# BaseBoard.net
KiCad netlist of a schematic drawn in EAGLE
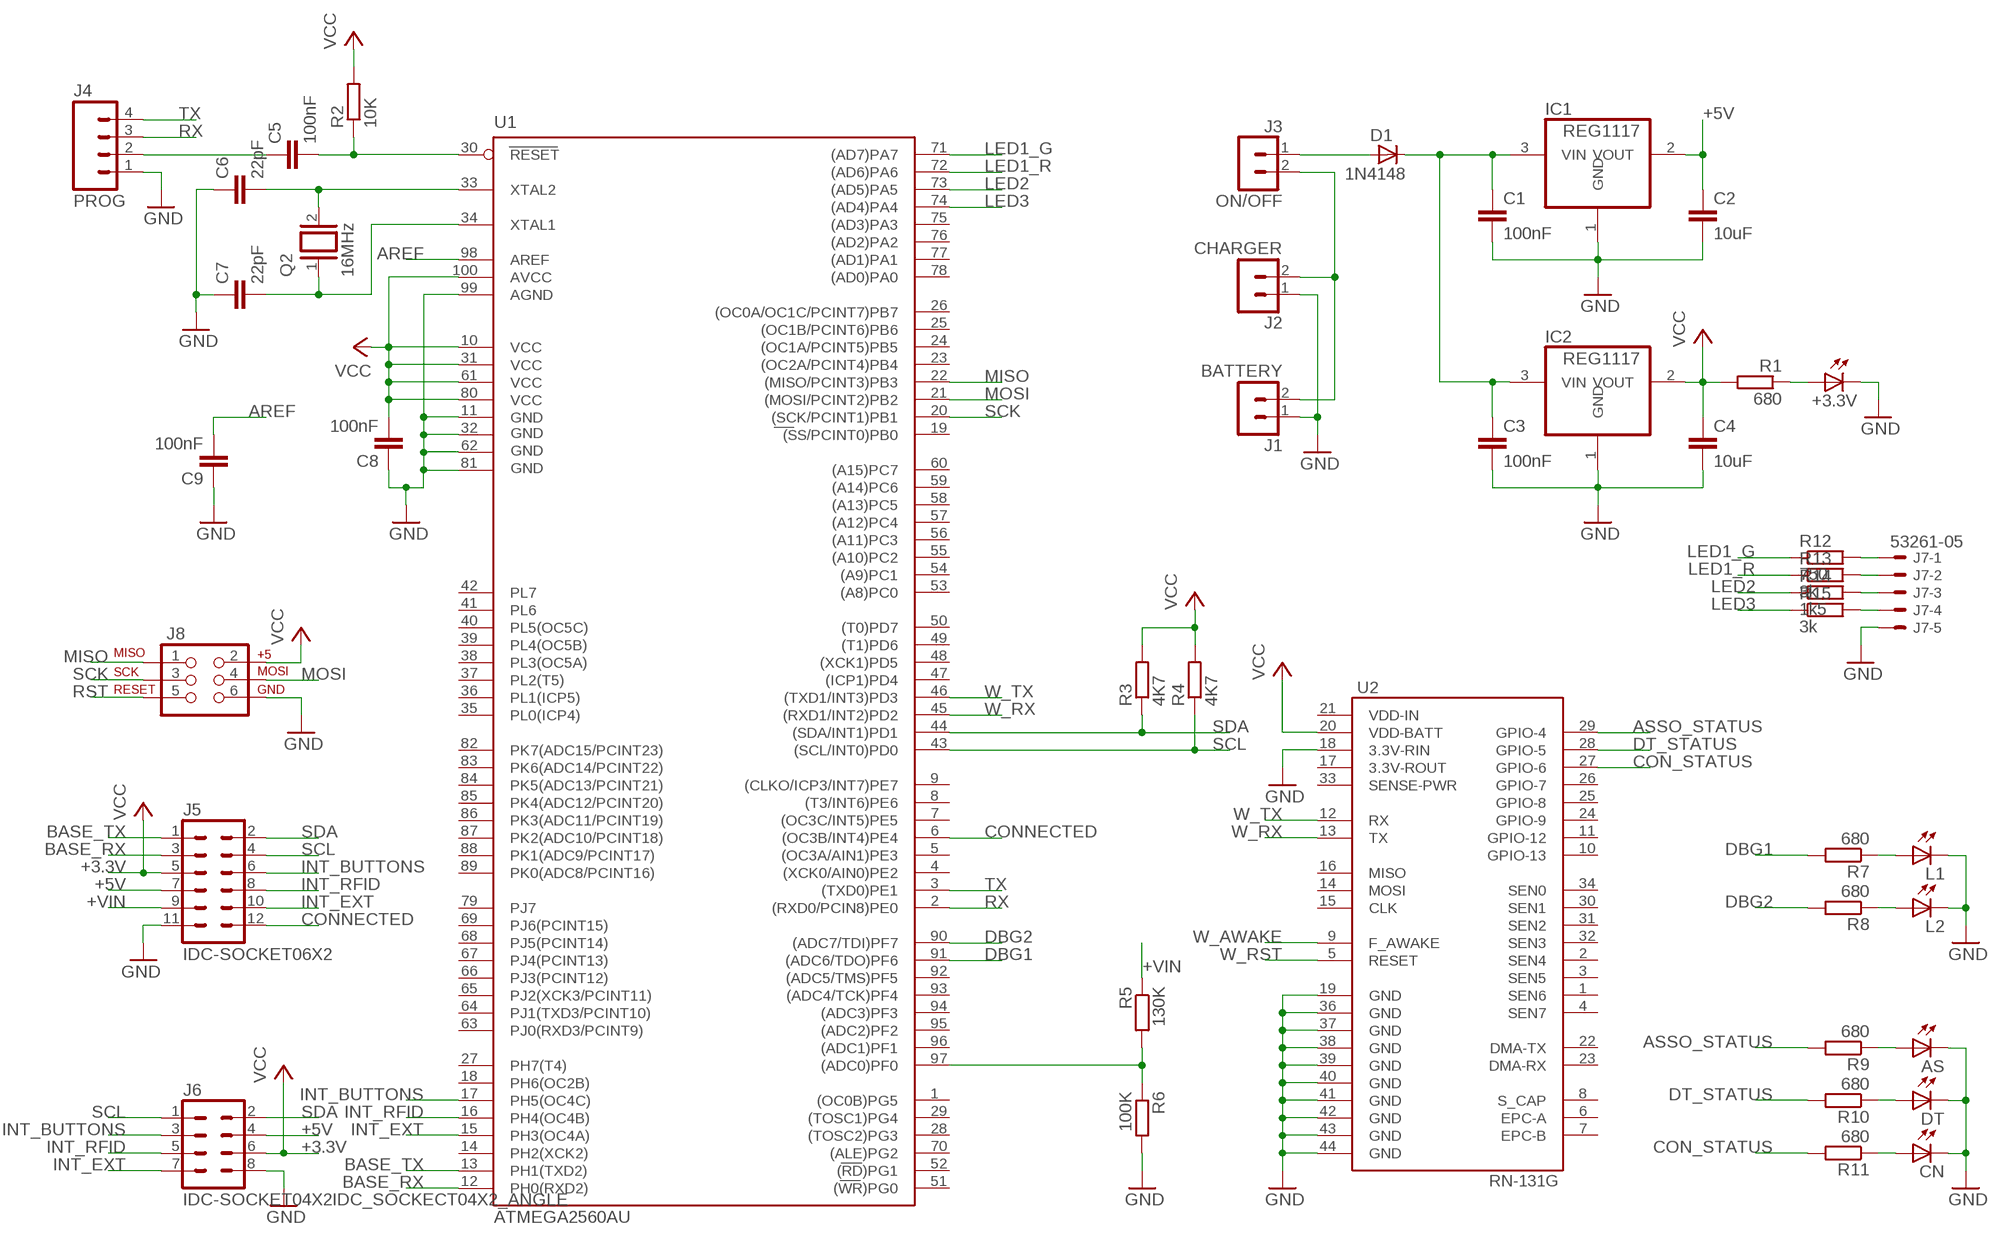
[diagram p0: schematic, sheet 1]

(export (version "E")
  (design (tool "Eeschema 10.0.6"))
  (components
    (comp (ref "+3.3V")
      (value "LEDSML0805")
      (footprint "eagle-import:SML0805")
      (libsource (lib "eagle-import") (part "LEDSML0805"))
    )
    (comp (ref "AS")
      (value "LEDSML0805")
      (footprint "eagle-import:SML0805")
      (libsource (lib "eagle-import") (part "LEDSML0805"))
    )
    (comp (ref "C1")
      (value "100nF")
      (footprint "eagle-import:C0805")
      (libsource (lib "eagle-import") (part "C-EUC0805"))
    )
    (comp (ref "C2")
      (value "10uF")
      (footprint "eagle-import:C0805")
      (libsource (lib "eagle-import") (part "C-EUC0805"))
    )
    (comp (ref "C3")
      (value "100nF")
      (footprint "eagle-import:C0805")
      (libsource (lib "eagle-import") (part "C-EUC0805"))
    )
    (comp (ref "C4")
      (value "10uF")
      (footprint "eagle-import:C0805")
      (libsource (lib "eagle-import") (part "C-EUC0805"))
    )
    (comp (ref "C5")
      (value "100nF")
      (footprint "eagle-import:C0805")
      (libsource (lib "eagle-import") (part "C-EUC0805"))
    )
    (comp (ref "C6")
      (value "22pF")
      (footprint "eagle-import:C0805")
      (libsource (lib "eagle-import") (part "C-EUC0805"))
    )
    (comp (ref "C7")
      (value "22pF")
      (footprint "eagle-import:C0805")
      (libsource (lib "eagle-import") (part "C-EUC0805"))
    )
    (comp (ref "C8")
      (value "100nF")
      (footprint "eagle-import:C0805")
      (libsource (lib "eagle-import") (part "C-EUC0805"))
    )
    (comp (ref "C9")
      (value "100nF")
      (footprint "eagle-import:C0805")
      (libsource (lib "eagle-import") (part "C-EUC0805"))
    )
    (comp (ref "CN")
      (value "LEDSML0805")
      (footprint "eagle-import:SML0805")
      (libsource (lib "eagle-import") (part "LEDSML0805"))
    )
    (comp (ref "D1")
      (value "1N4148")
      (footprint "eagle-import:D0805")
      (libsource (lib "eagle-import") (part "1N4148"))
    )
    (comp (ref "DT")
      (value "LEDSML0805")
      (footprint "eagle-import:SML0805")
      (libsource (lib "eagle-import") (part "LEDSML0805"))
    )
    (comp (ref "IC1")
      (value "REG1117")
      (footprint "eagle-import:SOT223")
      (libsource (lib "eagle-import") (part "REG1117"))
    )
    (comp (ref "IC2")
      (value "REG1117")
      (footprint "eagle-import:SOT223")
      (libsource (lib "eagle-import") (part "REG1117"))
    )
    (comp (ref "J1")
      (value "BATTERY")
      (footprint "eagle-import:CON_2P_SMD")
      (libsource (lib "eagle-import") (part "CON02"))
    )
    (comp (ref "J2")
      (value "CHARGER")
      (footprint "eagle-import:CON_2P_SMD")
      (libsource (lib "eagle-import") (part "CON02"))
    )
    (comp (ref "J3")
      (value "ON/OFF")
      (footprint "eagle-import:CON_2P_SMD")
      (libsource (lib "eagle-import") (part "CON02"))
    )
    (comp (ref "J4")
      (value "PROG")
      (footprint "eagle-import:1X04")
      (libsource (lib "eagle-import") (part "M04PTH"))
    )
    (comp (ref "J5")
      (value "IDC-SOCKET06X2")
      (footprint "eagle-import:SOCKET06X2")
      (libsource (lib "eagle-import") (part "IDC-SOCKET06X2"))
    )
    (comp (ref "J6")
      (value "IDC-SOCKET04X2IDC_SOCKECT04X2_ANGLE")
      (footprint "eagle-import:SOCKET04X2_ANGLE")
      (libsource (lib "eagle-import") (part "IDC-SOCKET04X2IDC_SOCKECT04X2_ANGLE"))
    )
    (comp (ref "J7")
      (value "53261-05")
      (footprint "eagle-import:53261-05")
      (libsource (lib "eagle-import") (part "53?-05261"))
    )
    (comp (ref "J8")
      (value "AVR_SPI_PRG_6NS")
      (footprint "eagle-import:2X3-NS")
      (libsource (lib "eagle-import") (part "AVR_SPI_PRG_6NS"))
    )
    (comp (ref "L1")
      (value "LEDSML0805")
      (footprint "eagle-import:SML0805")
      (libsource (lib "eagle-import") (part "LEDSML0805"))
    )
    (comp (ref "L2")
      (value "LEDSML0805")
      (footprint "eagle-import:SML0805")
      (libsource (lib "eagle-import") (part "LEDSML0805"))
    )
    (comp (ref "Q2")
      (value "16MHz")
      (footprint "eagle-import:QS")
      (libsource (lib "eagle-import") (part "XTAL/S"))
    )
    (comp (ref "R1")
      (value "680")
      (footprint "eagle-import:R0805")
      (libsource (lib "eagle-import") (part "R-EU_R0805"))
    )
    (comp (ref "R2")
      (value "10K")
      (footprint "eagle-import:R0805")
      (libsource (lib "eagle-import") (part "R-EU_R0805"))
    )
    (comp (ref "R3")
      (value "4K7")
      (footprint "eagle-import:R0805")
      (libsource (lib "eagle-import") (part "R-EU_R0805"))
    )
    (comp (ref "R4")
      (value "4K7")
      (footprint "eagle-import:R0805")
      (libsource (lib "eagle-import") (part "R-EU_R0805"))
    )
    (comp (ref "R5")
      (value "130K")
      (footprint "eagle-import:R0805")
      (libsource (lib "eagle-import") (part "R-EU_R0805"))
    )
    (comp (ref "R6")
      (value "100K")
      (footprint "eagle-import:R0805")
      (libsource (lib "eagle-import") (part "R-EU_R0805"))
    )
    (comp (ref "R7")
      (value "680")
      (footprint "eagle-import:R0805")
      (libsource (lib "eagle-import") (part "R-EU_R0805"))
    )
    (comp (ref "R8")
      (value "680")
      (footprint "eagle-import:R0805")
      (libsource (lib "eagle-import") (part "R-EU_R0805"))
    )
    (comp (ref "R9")
      (value "680")
      (footprint "eagle-import:R0805")
      (libsource (lib "eagle-import") (part "R-EU_R0805"))
    )
    (comp (ref "R10")
      (value "680")
      (footprint "eagle-import:R0805")
      (libsource (lib "eagle-import") (part "R-EU_R0805"))
    )
    (comp (ref "R11")
      (value "680")
      (footprint "eagle-import:R0805")
      (libsource (lib "eagle-import") (part "R-EU_R0805"))
    )
    (comp (ref "R12")
      (value "750")
      (footprint "eagle-import:R0805")
      (libsource (lib "eagle-import") (part "R-EU_R0805"))
    )
    (comp (ref "R13")
      (value "3k")
      (footprint "eagle-import:R0805")
      (libsource (lib "eagle-import") (part "R-EU_R0805"))
    )
    (comp (ref "R14")
      (value "1k5")
      (footprint "eagle-import:R0805")
      (libsource (lib "eagle-import") (part "R-EU_R0805"))
    )
    (comp (ref "R15")
      (value "3k")
      (footprint "eagle-import:R0805")
      (libsource (lib "eagle-import") (part "R-EU_R0805"))
    )
    (comp (ref "U1")
      (value "ATMEGA2560AU")
      (footprint "eagle-import:TQFP100")
      (libsource (lib "eagle-import") (part "ATMEGA2560AU"))
    )
    (comp (ref "U2")
      (value "RN-131G")
      (footprint "eagle-import:RN-131G")
      (libsource (lib "eagle-import") (part "RN-131G"))
    )
  )
  (nets
    (net (code "1") (name "/+5V") (class "Default")
      (node (ref "C2") (pin "1") (pinfunction "1_1") (pintype "passive"))
      (node (ref "IC1") (pin "2") (pinfunction "VOUT_2") (pintype "output"))
      (node (ref "J5") (pin "7") (pinfunction "7_7") (pintype "passive"))
      (node (ref "J6") (pin "4") (pinfunction "4_4") (pintype "passive"))
    )
    (net (code "2") (name "/+VIN") (class "Default")
      (node (ref "C1") (pin "1") (pinfunction "1_1") (pintype "passive"))
      (node (ref "C3") (pin "1") (pinfunction "1_1") (pintype "passive"))
      (node (ref "D1") (pin "C") (pinfunction "C_C") (pintype "passive"))
      (node (ref "IC1") (pin "3") (pinfunction "VIN_3") (pintype "input"))
      (node (ref "IC2") (pin "3") (pinfunction "VIN_3") (pintype "input"))
      (node (ref "J5") (pin "9") (pinfunction "9_9") (pintype "passive"))
      (node (ref "R5") (pin "1") (pinfunction "1_1") (pintype "passive"))
    )
    (net (code "3") (name "/AREF") (class "Default")
      (node (ref "C9") (pin "2") (pinfunction "2_2") (pintype "passive"))
      (node (ref "U1") (pin "98") (pinfunction "AREF_98") (pintype "bidirectional"))
    )
    (net (code "4") (name "/ASSO_STATUS") (class "Default")
      (node (ref "R9") (pin "2") (pinfunction "2_2") (pintype "passive"))
      (node (ref "U2") (pin "29") (pinfunction "GPIO-4_29") (pintype "bidirectional"))
    )
    (net (code "5") (name "/BASE_RX") (class "Default")
      (node (ref "J5") (pin "3") (pinfunction "3_3") (pintype "passive"))
      (node (ref "U1") (pin "12") (pinfunction "PH0(RXD2)_12") (pintype "bidirectional"))
    )
    (net (code "6") (name "/BASE_TX") (class "Default")
      (node (ref "J5") (pin "1") (pinfunction "1_1") (pintype "passive"))
      (node (ref "U1") (pin "13") (pinfunction "PH1(TXD2)_13") (pintype "bidirectional"))
    )
    (net (code "7") (name "/CONNECTED") (class "Default")
      (node (ref "J5") (pin "12") (pinfunction "12_12") (pintype "passive"))
      (node (ref "U1") (pin "6") (pinfunction "(OC3B/INT4)PE4_6") (pintype "bidirectional"))
    )
    (net (code "8") (name "/CON_STATUS") (class "Default")
      (node (ref "R11") (pin "2") (pinfunction "2_2") (pintype "passive"))
      (node (ref "U2") (pin "27") (pinfunction "GPIO-6_27") (pintype "bidirectional"))
    )
    (net (code "9") (name "/DBG1") (class "Default")
      (node (ref "R7") (pin "2") (pinfunction "2_2") (pintype "passive"))
      (node (ref "U1") (pin "91") (pinfunction "(ADC6/TDO)PF6_91") (pintype "bidirectional"))
    )
    (net (code "10") (name "/DBG2") (class "Default")
      (node (ref "R8") (pin "2") (pinfunction "2_2") (pintype "passive"))
      (node (ref "U1") (pin "90") (pinfunction "(ADC7/TDI)PF7_90") (pintype "bidirectional"))
    )
    (net (code "11") (name "/DT_STATUS") (class "Default")
      (node (ref "R10") (pin "2") (pinfunction "2_2") (pintype "passive"))
      (node (ref "U2") (pin "28") (pinfunction "GPIO-5_28") (pintype "bidirectional"))
    )
    (net (code "12") (name "/INT_BUTTONS") (class "Default")
      (node (ref "J5") (pin "6") (pinfunction "6_6") (pintype "passive"))
      (node (ref "J6") (pin "3") (pinfunction "3_3") (pintype "passive"))
      (node (ref "U1") (pin "17") (pinfunction "PH5(OC4C)_17") (pintype "bidirectional"))
    )
    (net (code "13") (name "/INT_EXT") (class "Default")
      (node (ref "J5") (pin "10") (pinfunction "10_10") (pintype "passive"))
      (node (ref "J6") (pin "7") (pinfunction "7_7") (pintype "passive"))
      (node (ref "U1") (pin "15") (pinfunction "PH3(OC4A)_15") (pintype "bidirectional"))
    )
    (net (code "14") (name "/INT_RFID") (class "Default")
      (node (ref "J5") (pin "8") (pinfunction "8_8") (pintype "passive"))
      (node (ref "J6") (pin "5") (pinfunction "5_5") (pintype "passive"))
      (node (ref "U1") (pin "16") (pinfunction "PH4(OC4B)_16") (pintype "bidirectional"))
    )
    (net (code "15") (name "/LED1_G") (class "Default")
      (node (ref "R12") (pin "1") (pinfunction "1_1") (pintype "passive"))
      (node (ref "U1") (pin "71") (pinfunction "(AD7)PA7_71") (pintype "bidirectional"))
    )
    (net (code "16") (name "/LED1_R") (class "Default")
      (node (ref "R13") (pin "1") (pinfunction "1_1") (pintype "passive"))
      (node (ref "U1") (pin "72") (pinfunction "(AD6)PA6_72") (pintype "bidirectional"))
    )
    (net (code "17") (name "/LED2") (class "Default")
      (node (ref "R14") (pin "1") (pinfunction "1_1") (pintype "passive"))
      (node (ref "U1") (pin "73") (pinfunction "(AD5)PA5_73") (pintype "bidirectional"))
    )
    (net (code "18") (name "/LED3") (class "Default")
      (node (ref "R15") (pin "1") (pinfunction "1_1") (pintype "passive"))
      (node (ref "U1") (pin "74") (pinfunction "(AD4)PA4_74") (pintype "bidirectional"))
    )
    (net (code "19") (name "/MISO") (class "Default")
      (node (ref "J8") (pin "1") (pinfunction "1_1") (pintype "passive"))
      (node (ref "U1") (pin "22") (pinfunction "(MISO/PCINT3)PB3_22") (pintype "bidirectional"))
    )
    (net (code "20") (name "/MOSI") (class "Default")
      (node (ref "J8") (pin "4") (pinfunction "4_4") (pintype "passive"))
      (node (ref "U1") (pin "21") (pinfunction "(MOSI/PCINT2)PB2_21") (pintype "bidirectional"))
    )
    (net (code "21") (name "/RST") (class "Default")
      (node (ref "C5") (pin "2") (pinfunction "2_2") (pintype "passive"))
      (node (ref "J8") (pin "5") (pinfunction "5_5") (pintype "passive"))
      (node (ref "R2") (pin "1") (pinfunction "1_1") (pintype "passive"))
      (node (ref "U1") (pin "30") (pinfunction "RESET_30") (pintype "input"))
    )
    (net (code "22") (name "/RX") (class "Default")
      (node (ref "J4") (pin "3") (pinfunction "3_3") (pintype "passive"))
      (node (ref "U1") (pin "2") (pinfunction "(RXD0/PCIN8)PE0_2") (pintype "bidirectional"))
    )
    (net (code "23") (name "/SCK") (class "Default")
      (node (ref "J8") (pin "3") (pinfunction "3_3") (pintype "passive"))
      (node (ref "U1") (pin "20") (pinfunction "(SCK/PCINT1)PB1_20") (pintype "bidirectional"))
    )
    (net (code "24") (name "/SCL") (class "Default")
      (node (ref "J5") (pin "4") (pinfunction "4_4") (pintype "passive"))
      (node (ref "J6") (pin "1") (pinfunction "1_1") (pintype "passive"))
      (node (ref "R4") (pin "1") (pinfunction "1_1") (pintype "passive"))
      (node (ref "U1") (pin "43") (pinfunction "(SCL/INT0)PD0_43") (pintype "bidirectional"))
    )
    (net (code "25") (name "/SDA") (class "Default")
      (node (ref "J5") (pin "2") (pinfunction "2_2") (pintype "passive"))
      (node (ref "J6") (pin "2") (pinfunction "2_2") (pintype "passive"))
      (node (ref "R3") (pin "1") (pinfunction "1_1") (pintype "passive"))
      (node (ref "U1") (pin "44") (pinfunction "(SDA/INT1)PD1_44") (pintype "bidirectional"))
    )
    (net (code "26") (name "/TX") (class "Default")
      (node (ref "J4") (pin "4") (pinfunction "4_4") (pintype "passive"))
      (node (ref "U1") (pin "3") (pinfunction "(TXD0)PE1_3") (pintype "bidirectional"))
    )
    (net (code "27") (name "/W_AWAKE") (class "Default")
      (node (ref "U2") (pin "9") (pinfunction "F_AWAKE_9") (pintype "bidirectional"))
    )
    (net (code "28") (name "/W_RST") (class "Default")
      (node (ref "U2") (pin "5") (pinfunction "RESET_5") (pintype "bidirectional"))
    )
    (net (code "29") (name "/W_RX") (class "Default")
      (node (ref "U1") (pin "45") (pinfunction "(RXD1/INT2)PD2_45") (pintype "bidirectional"))
      (node (ref "U2") (pin "13") (pinfunction "TX_13") (pintype "bidirectional"))
    )
    (net (code "30") (name "/W_TX") (class "Default")
      (node (ref "U1") (pin "46") (pinfunction "(TXD1/INT3)PD3_46") (pintype "bidirectional"))
      (node (ref "U2") (pin "12") (pinfunction "RX_12") (pintype "bidirectional"))
    )
    (net (code "31") (name "GND") (class "Default")
      (node (ref "+3.3V") (pin "C") (pinfunction "C_C") (pintype "passive"))
      (node (ref "AS") (pin "C") (pinfunction "C_C") (pintype "passive"))
      (node (ref "C1") (pin "2") (pinfunction "2_2") (pintype "passive"))
      (node (ref "C2") (pin "2") (pinfunction "2_2") (pintype "passive"))
      (node (ref "C3") (pin "2") (pinfunction "2_2") (pintype "passive"))
      (node (ref "C4") (pin "2") (pinfunction "2_2") (pintype "passive"))
      (node (ref "C6") (pin "1") (pinfunction "1_1") (pintype "passive"))
      (node (ref "C7") (pin "1") (pinfunction "1_1") (pintype "passive"))
      (node (ref "C8") (pin "1") (pinfunction "1_1") (pintype "passive"))
      (node (ref "C9") (pin "1") (pinfunction "1_1") (pintype "passive"))
      (node (ref "CN") (pin "C") (pinfunction "C_C") (pintype "passive"))
      (node (ref "DT") (pin "C") (pinfunction "C_C") (pintype "passive"))
      (node (ref "IC1") (pin "1") (pinfunction "GND_1") (pintype "power_in"))
      (node (ref "IC2") (pin "1") (pinfunction "GND_1") (pintype "power_in"))
      (node (ref "J1") (pin "1") (pinfunction "1_1") (pintype "passive"))
      (node (ref "J2") (pin "1") (pinfunction "1_1") (pintype "passive"))
      (node (ref "J4") (pin "1") (pinfunction "1_1") (pintype "passive"))
      (node (ref "J5") (pin "11") (pinfunction "11_11") (pintype "passive"))
      (node (ref "J6") (pin "8") (pinfunction "8_8") (pintype "passive"))
      (node (ref "J7") (pin "5") (pinfunction "S_5") (pintype "passive"))
      (node (ref "J8") (pin "6") (pinfunction "6_6") (pintype "passive"))
      (node (ref "L1") (pin "C") (pinfunction "C_C") (pintype "passive"))
      (node (ref "L2") (pin "C") (pinfunction "C_C") (pintype "passive"))
      (node (ref "R6") (pin "2") (pinfunction "2_2") (pintype "passive"))
      (node (ref "U1") (pin "11") (pinfunction "GND_11") (pintype "power_in"))
      (node (ref "U1") (pin "32") (pinfunction "GND1_32") (pintype "power_in"))
      (node (ref "U1") (pin "62") (pinfunction "GND2_62") (pintype "power_in"))
      (node (ref "U1") (pin "81") (pinfunction "GND3_81") (pintype "power_in"))
      (node (ref "U1") (pin "99") (pinfunction "AGND_99") (pintype "power_in"))
      (node (ref "U2") (pin "18") (pinfunction "3.3V-RIN_18") (pintype "bidirectional"))
      (node (ref "U2") (pin "19") (pinfunction "GND_19") (pintype "bidirectional"))
      (node (ref "U2") (pin "36") (pinfunction "GND_36") (pintype "bidirectional"))
      (node (ref "U2") (pin "37") (pinfunction "GND_37") (pintype "bidirectional"))
      (node (ref "U2") (pin "38") (pinfunction "GND_38") (pintype "bidirectional"))
      (node (ref "U2") (pin "39") (pinfunction "GND_39") (pintype "bidirectional"))
      (node (ref "U2") (pin "40") (pinfunction "GND_40") (pintype "bidirectional"))
      (node (ref "U2") (pin "41") (pinfunction "GND_41") (pintype "bidirectional"))
      (node (ref "U2") (pin "42") (pinfunction "GND_42") (pintype "bidirectional"))
      (node (ref "U2") (pin "43") (pinfunction "GND_43") (pintype "bidirectional"))
      (node (ref "U2") (pin "44") (pinfunction "GND_44") (pintype "bidirectional"))
    )
    (net (code "32") (name "Net-(+3.3V-PadA)") (class "Default")
      (node (ref "+3.3V") (pin "A") (pinfunction "A_A") (pintype "passive"))
      (node (ref "R1") (pin "1") (pinfunction "1_1") (pintype "passive"))
    )
    (net (code "33") (name "Net-(AS-PadA)") (class "Default")
      (node (ref "AS") (pin "A") (pinfunction "A_A") (pintype "passive"))
      (node (ref "R9") (pin "1") (pinfunction "1_1") (pintype "passive"))
    )
    (net (code "34") (name "Net-(C5-Pad1)") (class "Default")
      (node (ref "C5") (pin "1") (pinfunction "1_1") (pintype "passive"))
      (node (ref "J4") (pin "2") (pinfunction "2_2") (pintype "passive"))
    )
    (net (code "35") (name "Net-(CN-PadA)") (class "Default")
      (node (ref "CN") (pin "A") (pinfunction "A_A") (pintype "passive"))
      (node (ref "R11") (pin "1") (pinfunction "1_1") (pintype "passive"))
    )
    (net (code "36") (name "Net-(D1-PadA)") (class "Default")
      (node (ref "D1") (pin "A") (pinfunction "A_A") (pintype "passive"))
      (node (ref "J3") (pin "1") (pinfunction "1_1") (pintype "passive"))
    )
    (net (code "37") (name "Net-(DT-PadA)") (class "Default")
      (node (ref "DT") (pin "A") (pinfunction "A_A") (pintype "passive"))
      (node (ref "R10") (pin "1") (pinfunction "1_1") (pintype "passive"))
    )
    (net (code "38") (name "Net-(J1-Pad2)") (class "Default")
      (node (ref "J1") (pin "2") (pinfunction "2_2") (pintype "passive"))
      (node (ref "J2") (pin "2") (pinfunction "2_2") (pintype "passive"))
      (node (ref "J3") (pin "2") (pinfunction "2_2") (pintype "passive"))
    )
    (net (code "39") (name "Net-(J7A-S)") (class "Default")
      (node (ref "J7") (pin "1") (pinfunction "S_1") (pintype "passive"))
      (node (ref "R12") (pin "2") (pinfunction "2_2") (pintype "passive"))
    )
    (net (code "40") (name "Net-(J7B-S)") (class "Default")
      (node (ref "J7") (pin "2") (pinfunction "S_2") (pintype "passive"))
      (node (ref "R13") (pin "2") (pinfunction "2_2") (pintype "passive"))
    )
    (net (code "41") (name "Net-(J7C-S)") (class "Default")
      (node (ref "J7") (pin "3") (pinfunction "S_3") (pintype "passive"))
      (node (ref "R14") (pin "2") (pinfunction "2_2") (pintype "passive"))
    )
    (net (code "42") (name "Net-(J7D-S)") (class "Default")
      (node (ref "J7") (pin "4") (pinfunction "S_4") (pintype "passive"))
      (node (ref "R15") (pin "2") (pinfunction "2_2") (pintype "passive"))
    )
    (net (code "43") (name "Net-(L1-PadA)") (class "Default")
      (node (ref "L1") (pin "A") (pinfunction "A_A") (pintype "passive"))
      (node (ref "R7") (pin "1") (pinfunction "1_1") (pintype "passive"))
    )
    (net (code "44") (name "Net-(L2-PadA)") (class "Default")
      (node (ref "L2") (pin "A") (pinfunction "A_A") (pintype "passive"))
      (node (ref "R8") (pin "1") (pinfunction "1_1") (pintype "passive"))
    )
    (net (code "45") (name "Net-(U1-(ADC0)PF0)") (class "Default")
      (node (ref "R5") (pin "2") (pinfunction "2_2") (pintype "passive"))
      (node (ref "R6") (pin "1") (pinfunction "1_1") (pintype "passive"))
      (node (ref "U1") (pin "97") (pinfunction "(ADC0)PF0_97") (pintype "bidirectional"))
    )
    (net (code "46") (name "Net-(U1-XTAL1)") (class "Default")
      (node (ref "C7") (pin "2") (pinfunction "2_2") (pintype "passive"))
      (node (ref "Q2") (pin "1") (pinfunction "1_1") (pintype "passive"))
      (node (ref "U1") (pin "34") (pinfunction "XTAL1_34") (pintype "input"))
    )
    (net (code "47") (name "Net-(U1-XTAL2)") (class "Default")
      (node (ref "C6") (pin "2") (pinfunction "2_2") (pintype "passive"))
      (node (ref "Q2") (pin "2") (pinfunction "2_2") (pintype "passive"))
      (node (ref "U1") (pin "33") (pinfunction "XTAL2_33") (pintype "output"))
    )
    (net (code "48") (name "VCC") (class "Default")
      (node (ref "C4") (pin "1") (pinfunction "1_1") (pintype "passive"))
      (node (ref "C8") (pin "2") (pinfunction "2_2") (pintype "passive"))
      (node (ref "IC2") (pin "2") (pinfunction "VOUT_2") (pintype "output"))
      (node (ref "J5") (pin "5") (pinfunction "5_5") (pintype "passive"))
      (node (ref "J6") (pin "6") (pinfunction "6_6") (pintype "passive"))
      (node (ref "J8") (pin "2") (pinfunction "2_2") (pintype "passive"))
      (node (ref "R1") (pin "2") (pinfunction "2_2") (pintype "passive"))
      (node (ref "R2") (pin "2") (pinfunction "2_2") (pintype "passive"))
      (node (ref "R3") (pin "2") (pinfunction "2_2") (pintype "passive"))
      (node (ref "R4") (pin "2") (pinfunction "2_2") (pintype "passive"))
      (node (ref "U1") (pin "10") (pinfunction "VCC_10") (pintype "power_in"))
      (node (ref "U1") (pin "100") (pinfunction "AVCC_100") (pintype "power_in"))
      (node (ref "U1") (pin "31") (pinfunction "VCC1_31") (pintype "power_in"))
      (node (ref "U1") (pin "61") (pinfunction "VCC2_61") (pintype "power_in"))
      (node (ref "U1") (pin "80") (pinfunction "VCC3_80") (pintype "power_in"))
      (node (ref "U2") (pin "20") (pinfunction "VDD-BATT_20") (pintype "bidirectional"))
    )
    (net (code "49") (name "unconnected-(U1-(A8)PC0-Pad53)") (class "Default")
      (node (ref "U1") (pin "53") (pinfunction "(A8)PC0_53") (pintype "bidirectional"))
    )
    (net (code "50") (name "unconnected-(U1-(A9)PC1-Pad54)") (class "Default")
      (node (ref "U1") (pin "54") (pinfunction "(A9)PC1_54") (pintype "bidirectional"))
    )
    (net (code "51") (name "unconnected-(U1-(A10)PC2-Pad55)") (class "Default")
      (node (ref "U1") (pin "55") (pinfunction "(A10)PC2_55") (pintype "bidirectional"))
    )
    (net (code "52") (name "unconnected-(U1-(A11)PC3-Pad56)") (class "Default")
      (node (ref "U1") (pin "56") (pinfunction "(A11)PC3_56") (pintype "bidirectional"))
    )
    (net (code "53") (name "unconnected-(U1-(A12)PC4-Pad57)") (class "Default")
      (node (ref "U1") (pin "57") (pinfunction "(A12)PC4_57") (pintype "bidirectional"))
    )
    (net (code "54") (name "unconnected-(U1-(A13)PC5-Pad58)") (class "Default")
      (node (ref "U1") (pin "58") (pinfunction "(A13)PC5_58") (pintype "bidirectional"))
    )
    (net (code "55") (name "unconnected-(U1-(A14)PC6-Pad59)") (class "Default")
      (node (ref "U1") (pin "59") (pinfunction "(A14)PC6_59") (pintype "bidirectional"))
    )
    (net (code "56") (name "unconnected-(U1-(A15)PC7-Pad60)") (class "Default")
      (node (ref "U1") (pin "60") (pinfunction "(A15)PC7_60") (pintype "bidirectional"))
    )
    (net (code "57") (name "unconnected-(U1-(AD0)PA0-Pad78)") (class "Default")
      (node (ref "U1") (pin "78") (pinfunction "(AD0)PA0_78") (pintype "bidirectional"))
    )
    (net (code "58") (name "unconnected-(U1-(AD1)PA1-Pad77)") (class "Default")
      (node (ref "U1") (pin "77") (pinfunction "(AD1)PA1_77") (pintype "bidirectional"))
    )
    (net (code "59") (name "unconnected-(U1-(AD2)PA2-Pad76)") (class "Default")
      (node (ref "U1") (pin "76") (pinfunction "(AD2)PA2_76") (pintype "bidirectional"))
    )
    (net (code "60") (name "unconnected-(U1-(AD3)PA3-Pad75)") (class "Default")
      (node (ref "U1") (pin "75") (pinfunction "(AD3)PA3_75") (pintype "bidirectional"))
    )
    (net (code "61") (name "unconnected-(U1-(ADC1)PF1-Pad96)") (class "Default")
      (node (ref "U1") (pin "96") (pinfunction "(ADC1)PF1_96") (pintype "bidirectional"))
    )
    (net (code "62") (name "unconnected-(U1-(ADC2)PF2-Pad95)") (class "Default")
      (node (ref "U1") (pin "95") (pinfunction "(ADC2)PF2_95") (pintype "bidirectional"))
    )
    (net (code "63") (name "unconnected-(U1-(ADC3)PF3-Pad94)") (class "Default")
      (node (ref "U1") (pin "94") (pinfunction "(ADC3)PF3_94") (pintype "bidirectional"))
    )
    (net (code "64") (name "unconnected-(U1-(ADC4{slash}TCK)PF4-Pad93)") (class "Default")
      (node (ref "U1") (pin "93") (pinfunction "(ADC4/TCK)PF4_93") (pintype "bidirectional"))
    )
    (net (code "65") (name "unconnected-(U1-(ADC5{slash}TMS)PF5-Pad92)") (class "Default")
      (node (ref "U1") (pin "92") (pinfunction "(ADC5/TMS)PF5_92") (pintype "bidirectional"))
    )
    (net (code "66") (name "unconnected-(U1-(ALE)PG2-Pad70)") (class "Default")
      (node (ref "U1") (pin "70") (pinfunction "(ALE)PG2_70") (pintype "bidirectional"))
    )
    (net (code "67") (name "unconnected-(U1-(CLKO{slash}ICP3{slash}INT7)PE7-Pad9)") (class "Default")
      (node (ref "U1") (pin "9") (pinfunction "(CLKO/ICP3/INT7)PE7_9") (pintype "bidirectional"))
    )
    (net (code "68") (name "unconnected-(U1-(ICP1)PD4-Pad47)") (class "Default")
      (node (ref "U1") (pin "47") (pinfunction "(ICP1)PD4_47") (pintype "bidirectional"))
    )
    (net (code "69") (name "unconnected-(U1-(OC0A{slash}OC1C{slash}PCINT7)PB7-Pad26)") (class "Default")
      (node (ref "U1") (pin "26") (pinfunction "(OC0A/OC1C/PCINT7)PB7_26") (pintype "bidirectional"))
    )
    (net (code "70") (name "unconnected-(U1-(OC0B)PG5-Pad1)") (class "Default")
      (node (ref "U1") (pin "1") (pinfunction "(OC0B)PG5_1") (pintype "bidirectional"))
    )
    (net (code "71") (name "unconnected-(U1-(OC1A{slash}PCINT5)PB5-Pad24)") (class "Default")
      (node (ref "U1") (pin "24") (pinfunction "(OC1A/PCINT5)PB5_24") (pintype "bidirectional"))
    )
    (net (code "72") (name "unconnected-(U1-(OC1B{slash}PCINT6)PB6-Pad25)") (class "Default")
      (node (ref "U1") (pin "25") (pinfunction "(OC1B/PCINT6)PB6_25") (pintype "bidirectional"))
    )
    (net (code "73") (name "unconnected-(U1-(OC2A{slash}PCINT4)PB4-Pad23)") (class "Default")
      (node (ref "U1") (pin "23") (pinfunction "(OC2A/PCINT4)PB4_23") (pintype "bidirectional"))
    )
    (net (code "74") (name "unconnected-(U1-(OC3A{slash}AIN1)PE3-Pad5)") (class "Default")
      (node (ref "U1") (pin "5") (pinfunction "(OC3A/AIN1)PE3_5") (pintype "bidirectional"))
    )
    (net (code "75") (name "unconnected-(U1-(OC3C{slash}INT5)PE5-Pad7)") (class "Default")
      (node (ref "U1") (pin "7") (pinfunction "(OC3C/INT5)PE5_7") (pintype "bidirectional"))
    )
    (net (code "76") (name "unconnected-(U1-(RD)PG1-Pad52)") (class "Default")
      (node (ref "U1") (pin "52") (pinfunction "(RD)PG1_52") (pintype "bidirectional"))
    )
    (net (code "77") (name "unconnected-(U1-(SS{slash}PCINT0)PB0-Pad19)") (class "Default")
      (node (ref "U1") (pin "19") (pinfunction "(SS/PCINT0)PB0_19") (pintype "bidirectional"))
    )
    (net (code "78") (name "unconnected-(U1-(T0)PD7-Pad50)") (class "Default")
      (node (ref "U1") (pin "50") (pinfunction "(T0)PD7_50") (pintype "bidirectional"))
    )
    (net (code "79") (name "unconnected-(U1-(T1)PD6-Pad49)") (class "Default")
      (node (ref "U1") (pin "49") (pinfunction "(T1)PD6_49") (pintype "bidirectional"))
    )
    (net (code "80") (name "unconnected-(U1-(T3{slash}INT6)PE6-Pad8)") (class "Default")
      (node (ref "U1") (pin "8") (pinfunction "(T3/INT6)PE6_8") (pintype "bidirectional"))
    )
    (net (code "81") (name "unconnected-(U1-(TOSC1)PG4-Pad29)") (class "Default")
      (node (ref "U1") (pin "29") (pinfunction "(TOSC1)PG4_29") (pintype "bidirectional"))
    )
    (net (code "82") (name "unconnected-(U1-(TOSC2)PG3-Pad28)") (class "Default")
      (node (ref "U1") (pin "28") (pinfunction "(TOSC2)PG3_28") (pintype "bidirectional"))
    )
    (net (code "83") (name "unconnected-(U1-(WR)PG0-Pad51)") (class "Default")
      (node (ref "U1") (pin "51") (pinfunction "(WR)PG0_51") (pintype "bidirectional"))
    )
    (net (code "84") (name "unconnected-(U1-(XCK0{slash}AIN0)PE2-Pad4)") (class "Default")
      (node (ref "U1") (pin "4") (pinfunction "(XCK0/AIN0)PE2_4") (pintype "bidirectional"))
    )
    (net (code "85") (name "unconnected-(U1-(XCK1)PD5-Pad48)") (class "Default")
      (node (ref "U1") (pin "48") (pinfunction "(XCK1)PD5_48") (pintype "bidirectional"))
    )
    (net (code "86") (name "unconnected-(U1-PH2(XCK2)-Pad14)") (class "Default")
      (node (ref "U1") (pin "14") (pinfunction "PH2(XCK2)_14") (pintype "bidirectional"))
    )
    (net (code "87") (name "unconnected-(U1-PH6(OC2B)-Pad18)") (class "Default")
      (node (ref "U1") (pin "18") (pinfunction "PH6(OC2B)_18") (pintype "bidirectional"))
    )
    (net (code "88") (name "unconnected-(U1-PH7(T4)-Pad27)") (class "Default")
      (node (ref "U1") (pin "27") (pinfunction "PH7(T4)_27") (pintype "bidirectional"))
    )
    (net (code "89") (name "unconnected-(U1-PJ0(RXD3{slash}PCINT9)-Pad63)") (class "Default")
      (node (ref "U1") (pin "63") (pinfunction "PJ0(RXD3/PCINT9)_63") (pintype "bidirectional"))
    )
    (net (code "90") (name "unconnected-(U1-PJ1(TXD3{slash}PCINT10)-Pad64)") (class "Default")
      (node (ref "U1") (pin "64") (pinfunction "PJ1(TXD3/PCINT10)_64") (pintype "bidirectional"))
    )
    (net (code "91") (name "unconnected-(U1-PJ2(XCK3{slash}PCINT11)-Pad65)") (class "Default")
      (node (ref "U1") (pin "65") (pinfunction "PJ2(XCK3/PCINT11)_65") (pintype "bidirectional"))
    )
    (net (code "92") (name "unconnected-(U1-PJ3(PCINT12)-Pad66)") (class "Default")
      (node (ref "U1") (pin "66") (pinfunction "PJ3(PCINT12)_66") (pintype "bidirectional"))
    )
    (net (code "93") (name "unconnected-(U1-PJ4(PCINT13)-Pad67)") (class "Default")
      (node (ref "U1") (pin "67") (pinfunction "PJ4(PCINT13)_67") (pintype "bidirectional"))
    )
    (net (code "94") (name "unconnected-(U1-PJ5(PCINT14)-Pad68)") (class "Default")
      (node (ref "U1") (pin "68") (pinfunction "PJ5(PCINT14)_68") (pintype "bidirectional"))
    )
    (net (code "95") (name "unconnected-(U1-PJ6(PCINT15)-Pad69)") (class "Default")
      (node (ref "U1") (pin "69") (pinfunction "PJ6(PCINT15)_69") (pintype "bidirectional"))
    )
    (net (code "96") (name "unconnected-(U1-PJ7-Pad79)") (class "Default")
      (node (ref "U1") (pin "79") (pinfunction "PJ7_79") (pintype "bidirectional"))
    )
    (net (code "97") (name "unconnected-(U1-PK0(ADC8{slash}PCINT16)-Pad89)") (class "Default")
      (node (ref "U1") (pin "89") (pinfunction "PK0(ADC8/PCINT16)_89") (pintype "bidirectional"))
    )
    (net (code "98") (name "unconnected-(U1-PK1(ADC9{slash}PCINT17)-Pad88)") (class "Default")
      (node (ref "U1") (pin "88") (pinfunction "PK1(ADC9/PCINT17)_88") (pintype "bidirectional"))
    )
    (net (code "99") (name "unconnected-(U1-PK2(ADC10{slash}PCINT18)-Pad87)") (class "Default")
      (node (ref "U1") (pin "87") (pinfunction "PK2(ADC10/PCINT18)_87") (pintype "bidirectional"))
    )
    (net (code "100") (name "unconnected-(U1-PK3(ADC11{slash}PCINT19)-Pad86)") (class "Default")
      (node (ref "U1") (pin "86") (pinfunction "PK3(ADC11/PCINT19)_86") (pintype "bidirectional"))
    )
    (net (code "101") (name "unconnected-(U1-PK4(ADC12{slash}PCINT20)-Pad85)") (class "Default")
      (node (ref "U1") (pin "85") (pinfunction "PK4(ADC12/PCINT20)_85") (pintype "bidirectional"))
    )
    (net (code "102") (name "unconnected-(U1-PK5(ADC13{slash}PCINT21)-Pad84)") (class "Default")
      (node (ref "U1") (pin "84") (pinfunction "PK5(ADC13/PCINT21)_84") (pintype "bidirectional"))
    )
    (net (code "103") (name "unconnected-(U1-PK6(ADC14{slash}PCINT22)-Pad83)") (class "Default")
      (node (ref "U1") (pin "83") (pinfunction "PK6(ADC14/PCINT22)_83") (pintype "bidirectional"))
    )
    (net (code "104") (name "unconnected-(U1-PK7(ADC15{slash}PCINT23)-Pad82)") (class "Default")
      (node (ref "U1") (pin "82") (pinfunction "PK7(ADC15/PCINT23)_82") (pintype "bidirectional"))
    )
    (net (code "105") (name "unconnected-(U1-PL0(ICP4)-Pad35)") (class "Default")
      (node (ref "U1") (pin "35") (pinfunction "PL0(ICP4)_35") (pintype "bidirectional"))
    )
    (net (code "106") (name "unconnected-(U1-PL1(ICP5)-Pad36)") (class "Default")
      (node (ref "U1") (pin "36") (pinfunction "PL1(ICP5)_36") (pintype "bidirectional"))
    )
    (net (code "107") (name "unconnected-(U1-PL2(T5)-Pad37)") (class "Default")
      (node (ref "U1") (pin "37") (pinfunction "PL2(T5)_37") (pintype "bidirectional"))
    )
    (net (code "108") (name "unconnected-(U1-PL3(OC5A)-Pad38)") (class "Default")
      (node (ref "U1") (pin "38") (pinfunction "PL3(OC5A)_38") (pintype "bidirectional"))
    )
    (net (code "109") (name "unconnected-(U1-PL4(OC5B)-Pad39)") (class "Default")
      (node (ref "U1") (pin "39") (pinfunction "PL4(OC5B)_39") (pintype "bidirectional"))
    )
    (net (code "110") (name "unconnected-(U1-PL5(OC5C)-Pad40)") (class "Default")
      (node (ref "U1") (pin "40") (pinfunction "PL5(OC5C)_40") (pintype "bidirectional"))
    )
    (net (code "111") (name "unconnected-(U1-PL6-Pad41)") (class "Default")
      (node (ref "U1") (pin "41") (pinfunction "PL6_41") (pintype "bidirectional"))
    )
    (net (code "112") (name "unconnected-(U1-PL7-Pad42)") (class "Default")
      (node (ref "U1") (pin "42") (pinfunction "PL7_42") (pintype "bidirectional"))
    )
    (net (code "113") (name "unconnected-(U2-3.3V-ROUT-Pad17)") (class "Default")
      (node (ref "U2") (pin "17") (pinfunction "3.3V-ROUT_17") (pintype "bidirectional"))
    )
    (net (code "114") (name "unconnected-(U2-CLK-Pad15)") (class "Default")
      (node (ref "U2") (pin "15") (pinfunction "CLK_15") (pintype "bidirectional"))
    )
    (net (code "115") (name "unconnected-(U2-DMA-RX-Pad23)") (class "Default")
      (node (ref "U2") (pin "23") (pinfunction "DMA-RX_23") (pintype "bidirectional"))
    )
    (net (code "116") (name "unconnected-(U2-DMA-TX-Pad22)") (class "Default")
      (node (ref "U2") (pin "22") (pinfunction "DMA-TX_22") (pintype "bidirectional"))
    )
    (net (code "117") (name "unconnected-(U2-EPC-A-Pad6)") (class "Default")
      (node (ref "U2") (pin "6") (pinfunction "EPC-A_6") (pintype "bidirectional"))
    )
    (net (code "118") (name "unconnected-(U2-EPC-B-Pad7)") (class "Default")
      (node (ref "U2") (pin "7") (pinfunction "EPC-B_7") (pintype "bidirectional"))
    )
    (net (code "119") (name "unconnected-(U2-GPIO-7-Pad26)") (class "Default")
      (node (ref "U2") (pin "26") (pinfunction "GPIO-7_26") (pintype "bidirectional"))
    )
    (net (code "120") (name "unconnected-(U2-GPIO-8-Pad25)") (class "Default")
      (node (ref "U2") (pin "25") (pinfunction "GPIO-8_25") (pintype "bidirectional"))
    )
    (net (code "121") (name "unconnected-(U2-GPIO-9-Pad24)") (class "Default")
      (node (ref "U2") (pin "24") (pinfunction "GPIO-9_24") (pintype "bidirectional"))
    )
    (net (code "122") (name "unconnected-(U2-GPIO-12-Pad11)") (class "Default")
      (node (ref "U2") (pin "11") (pinfunction "GPIO-12_11") (pintype "bidirectional"))
    )
    (net (code "123") (name "unconnected-(U2-GPIO-13-Pad10)") (class "Default")
      (node (ref "U2") (pin "10") (pinfunction "GPIO-13_10") (pintype "bidirectional"))
    )
    (net (code "124") (name "unconnected-(U2-MISO-Pad16)") (class "Default")
      (node (ref "U2") (pin "16") (pinfunction "MISO_16") (pintype "bidirectional"))
    )
    (net (code "125") (name "unconnected-(U2-MOSI-Pad14)") (class "Default")
      (node (ref "U2") (pin "14") (pinfunction "MOSI_14") (pintype "bidirectional"))
    )
    (net (code "126") (name "unconnected-(U2-SEN0-Pad34)") (class "Default")
      (node (ref "U2") (pin "34") (pinfunction "SEN0_34") (pintype "bidirectional"))
    )
    (net (code "127") (name "unconnected-(U2-SEN1-Pad30)") (class "Default")
      (node (ref "U2") (pin "30") (pinfunction "SEN1_30") (pintype "bidirectional"))
    )
    (net (code "128") (name "unconnected-(U2-SEN2-Pad31)") (class "Default")
      (node (ref "U2") (pin "31") (pinfunction "SEN2_31") (pintype "bidirectional"))
    )
    (net (code "129") (name "unconnected-(U2-SEN3-Pad32)") (class "Default")
      (node (ref "U2") (pin "32") (pinfunction "SEN3_32") (pintype "bidirectional"))
    )
    (net (code "130") (name "unconnected-(U2-SEN4-Pad2)") (class "Default")
      (node (ref "U2") (pin "2") (pinfunction "SEN4_2") (pintype "bidirectional"))
    )
    (net (code "131") (name "unconnected-(U2-SEN5-Pad3)") (class "Default")
      (node (ref "U2") (pin "3") (pinfunction "SEN5_3") (pintype "bidirectional"))
    )
    (net (code "132") (name "unconnected-(U2-SEN6-Pad1)") (class "Default")
      (node (ref "U2") (pin "1") (pinfunction "SEN6_1") (pintype "bidirectional"))
    )
    (net (code "133") (name "unconnected-(U2-SEN7-Pad4)") (class "Default")
      (node (ref "U2") (pin "4") (pinfunction "SEN7_4") (pintype "bidirectional"))
    )
    (net (code "134") (name "unconnected-(U2-SENSE-PWR-Pad33)") (class "Default")
      (node (ref "U2") (pin "33") (pinfunction "SENSE-PWR_33") (pintype "bidirectional"))
    )
    (net (code "135") (name "unconnected-(U2-S_CAP-Pad8)") (class "Default")
      (node (ref "U2") (pin "8") (pinfunction "S_CAP_8") (pintype "bidirectional"))
    )
    (net (code "136") (name "unconnected-(U2-VDD-IN-Pad21)") (class "Default")
      (node (ref "U2") (pin "21") (pinfunction "VDD-IN_21") (pintype "bidirectional"))
    )
  )
)
